# sePentodeOutput.net
KiCad netlist of a schematic drawn in EAGLE
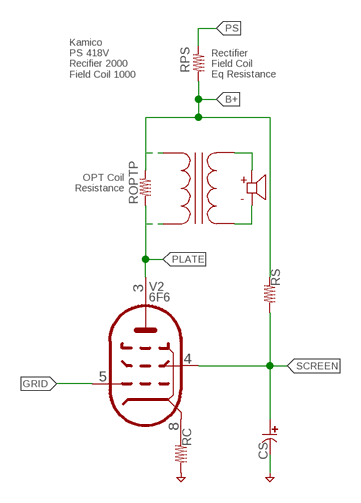
[diagram p0: schematic, sheet 1]

(export (version "E")
  (design (tool "Eeschema 10.0.6"))
  (components
    (comp (ref "CS")
      (value "C-POLARIZED-E-3")
      (footprint "eagle-import:C-E-3")
      (libsource (lib "eagle-import") (part "C-POLARIZED-E-3"))
    )
    (comp (ref "RC")
      (value "R-THRU-H-0.4")
      (footprint "eagle-import:R-THRU-H-0.4")
      (libsource (lib "eagle-import") (part "R-THRU-H-0.4"))
    )
    (comp (ref "ROPTP")
      (value "R-THRU-H-0.4")
      (footprint "eagle-import:R-THRU-H-0.4")
      (libsource (lib "eagle-import") (part "R-THRU-H-0.4"))
    )
    (comp (ref "RPS")
      (value "R-THRU-H-0.4")
      (footprint "eagle-import:R-THRU-H-0.4")
      (libsource (lib "eagle-import") (part "R-THRU-H-0.4"))
    )
    (comp (ref "RS")
      (value "R-THRU-H-0.4")
      (footprint "eagle-import:R-THRU-H-0.4")
      (libsource (lib "eagle-import") (part "R-THRU-H-0.4"))
    )
    (comp (ref "S")
      (value "4")
      (footprint "eagle-import:SPEAKER-CEM-1201-42")
      (fields (field (name "MF") "CUI") (field (name "MP") "CEM-1201_42_"))
      (libsource (lib "eagle-import") (part "SPEAKER-CEM-1201-42"))
    )
    (comp (ref "T")
      (value "TRANSFORMER-2-2")
      (footprint "eagle-import:TRANSFORMER-4-2-G")
      (libsource (lib "eagle-import") (part "TRANSFORMER-2-2"))
    )
    (comp (ref "V2")
      (value "6F6")
      (footprint "eagle-import:OKTAL")
      (libsource (lib "eagle-import") (part "6F6GT-P"))
    )
  )
  (nets
    (net (code "1") (name "B+") (class "Default")
      (node (ref "ROPTP") (pin "1") (pinfunction "1_1") (pintype "passive"))
      (node (ref "RPS") (pin "2") (pinfunction "2_2") (pintype "passive"))
      (node (ref "RS") (pin "1") (pinfunction "1_1") (pintype "passive"))
      (node (ref "T") (pin "1") (pinfunction "P1_1") (pintype "passive"))
    )
    (net (code "2") (name "GND") (class "Default")
      (node (ref "CS") (pin "-") (pinfunction "-_-") (pintype "passive"))
      (node (ref "RC") (pin "2") (pinfunction "2_2") (pintype "passive"))
    )
    (net (code "3") (name "GRID") (class "Default")
      (node (ref "V2") (pin "5") (pinfunction "PG_5") (pintype "passive"))
    )
    (net (code "4") (name "Net-(T-S1)") (class "Default")
      (node (ref "S") (pin "P") (pinfunction "P_P") (pintype "passive"))
      (node (ref "T") (pin "5") (pinfunction "S1_5") (pintype "passive"))
    )
    (net (code "5") (name "Net-(T-S2)") (class "Default")
      (node (ref "S") (pin "M") (pinfunction "M_M") (pintype "passive"))
      (node (ref "T") (pin "6") (pinfunction "S2_6") (pintype "passive"))
    )
    (net (code "6") (name "Net-(V2B-PK)") (class "Default")
      (node (ref "RC") (pin "1") (pinfunction "1_1") (pintype "passive"))
      (node (ref "V2") (pin "8") (pinfunction "PK_8") (pintype "passive"))
    )
    (net (code "7") (name "PLATE") (class "Default")
      (node (ref "ROPTP") (pin "2") (pinfunction "2_2") (pintype "passive"))
      (node (ref "T") (pin "2") (pinfunction "P2_2") (pintype "passive"))
      (node (ref "V2") (pin "3") (pinfunction "PA_3") (pintype "passive"))
    )
    (net (code "8") (name "PS") (class "Default")
      (node (ref "RPS") (pin "1") (pinfunction "1_1") (pintype "passive"))
    )
    (net (code "9") (name "SCREEN") (class "Default")
      (node (ref "CS") (pin "+") (pinfunction "+_+") (pintype "passive"))
      (node (ref "RS") (pin "2") (pinfunction "2_2") (pintype "passive"))
      (node (ref "V2") (pin "4") (pinfunction "PSG_4") (pintype "passive"))
    )
  )
)
